# DS1307_SMD_0603.net
KiCad netlist of a schematic drawn in EAGLE
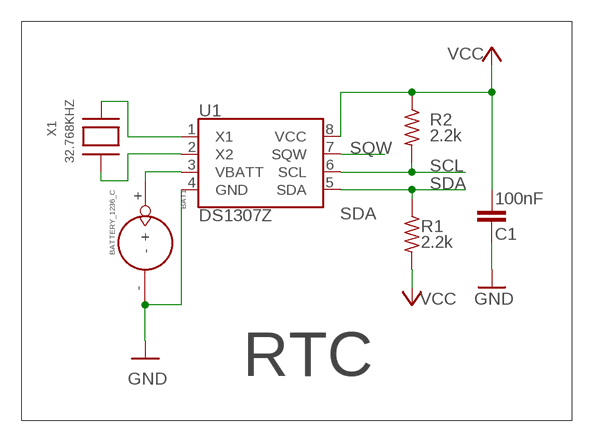
[diagram p0: schematic, sheet 1]

(export (version "E")
  (design (tool "Eeschema 10.0.6"))
  (components
    (comp (ref "BAT1")
      (value "BATTERY_1236_C")
      (footprint "eagle-import:BATTERY_1236_C")
      (libsource (lib "eagle-import") (part "BATTERY_1236_C"))
    )
    (comp (ref "C1")
      (value "100nF")
      (footprint "eagle-import:C0603")
      (libsource (lib "eagle-import") (part "C-EUC0603"))
    )
    (comp (ref "R1")
      (value "2.2k")
      (footprint "eagle-import:R0603")
      (libsource (lib "eagle-import") (part "R-US_R0603"))
    )
    (comp (ref "R2")
      (value "2.2k")
      (footprint "eagle-import:R0603")
      (libsource (lib "eagle-import") (part "R-US_R0603"))
    )
    (comp (ref "U1")
      (value "DS1307Z")
      (footprint "eagle-import:SO08-0.15")
      (libsource (lib "eagle-import") (part "DS1307Z"))
    )
    (comp (ref "X1")
      (value "32.768KHZ")
      (footprint "eagle-import:XTAL3215")
      (libsource (lib "eagle-import") (part "XTAL-3.2X1.5"))
    )
  )
  (nets
    (net (code "1") (name "/SCL") (class "Default")
      (node (ref "R2") (pin "2") (pinfunction "2_2") (pintype "passive"))
      (node (ref "U1") (pin "6") (pinfunction "SCL_6") (pintype "bidirectional"))
    )
    (net (code "2") (name "/SDA") (class "Default")
      (node (ref "R1") (pin "1") (pinfunction "1_1") (pintype "passive"))
      (node (ref "U1") (pin "5") (pinfunction "SDA_5") (pintype "bidirectional"))
    )
    (net (code "3") (name "/SQW") (class "Default")
      (node (ref "U1") (pin "7") (pinfunction "SQW_7") (pintype "bidirectional"))
    )
    (net (code "4") (name "GND") (class "Default")
      (node (ref "BAT1") (pin "-") (pinfunction "-_-") (pintype "bidirectional"))
      (node (ref "C1") (pin "1") (pinfunction "1_1") (pintype "passive"))
      (node (ref "U1") (pin "4") (pinfunction "GND_4") (pintype "bidirectional"))
    )
    (net (code "5") (name "Net-(U1-VBATT)") (class "Default")
      (node (ref "BAT1") (pin "+") (pinfunction "+_+") (pintype "bidirectional"))
      (node (ref "U1") (pin "3") (pinfunction "VBATT_3") (pintype "bidirectional"))
    )
    (net (code "6") (name "Net-(U1-X1)") (class "Default")
      (node (ref "U1") (pin "1") (pinfunction "X1_1") (pintype "bidirectional"))
      (node (ref "X1") (pin "P$2") (pinfunction "P$2_P$2") (pintype "bidirectional"))
    )
    (net (code "7") (name "Net-(U1-X2)") (class "Default")
      (node (ref "U1") (pin "2") (pinfunction "X2_2") (pintype "bidirectional"))
      (node (ref "X1") (pin "P$1") (pinfunction "P$1_P$1") (pintype "bidirectional"))
    )
    (net (code "8") (name "VCC") (class "Default")
      (node (ref "C1") (pin "2") (pinfunction "2_2") (pintype "passive"))
      (node (ref "R1") (pin "2") (pinfunction "2_2") (pintype "passive"))
      (node (ref "R2") (pin "1") (pinfunction "1_1") (pintype "passive"))
      (node (ref "U1") (pin "8") (pinfunction "VCC_8") (pintype "bidirectional"))
    )
  )
)
